# VESC_LANGYA.net
KiCad netlist of a schematic drawn in EasyEDA Pro
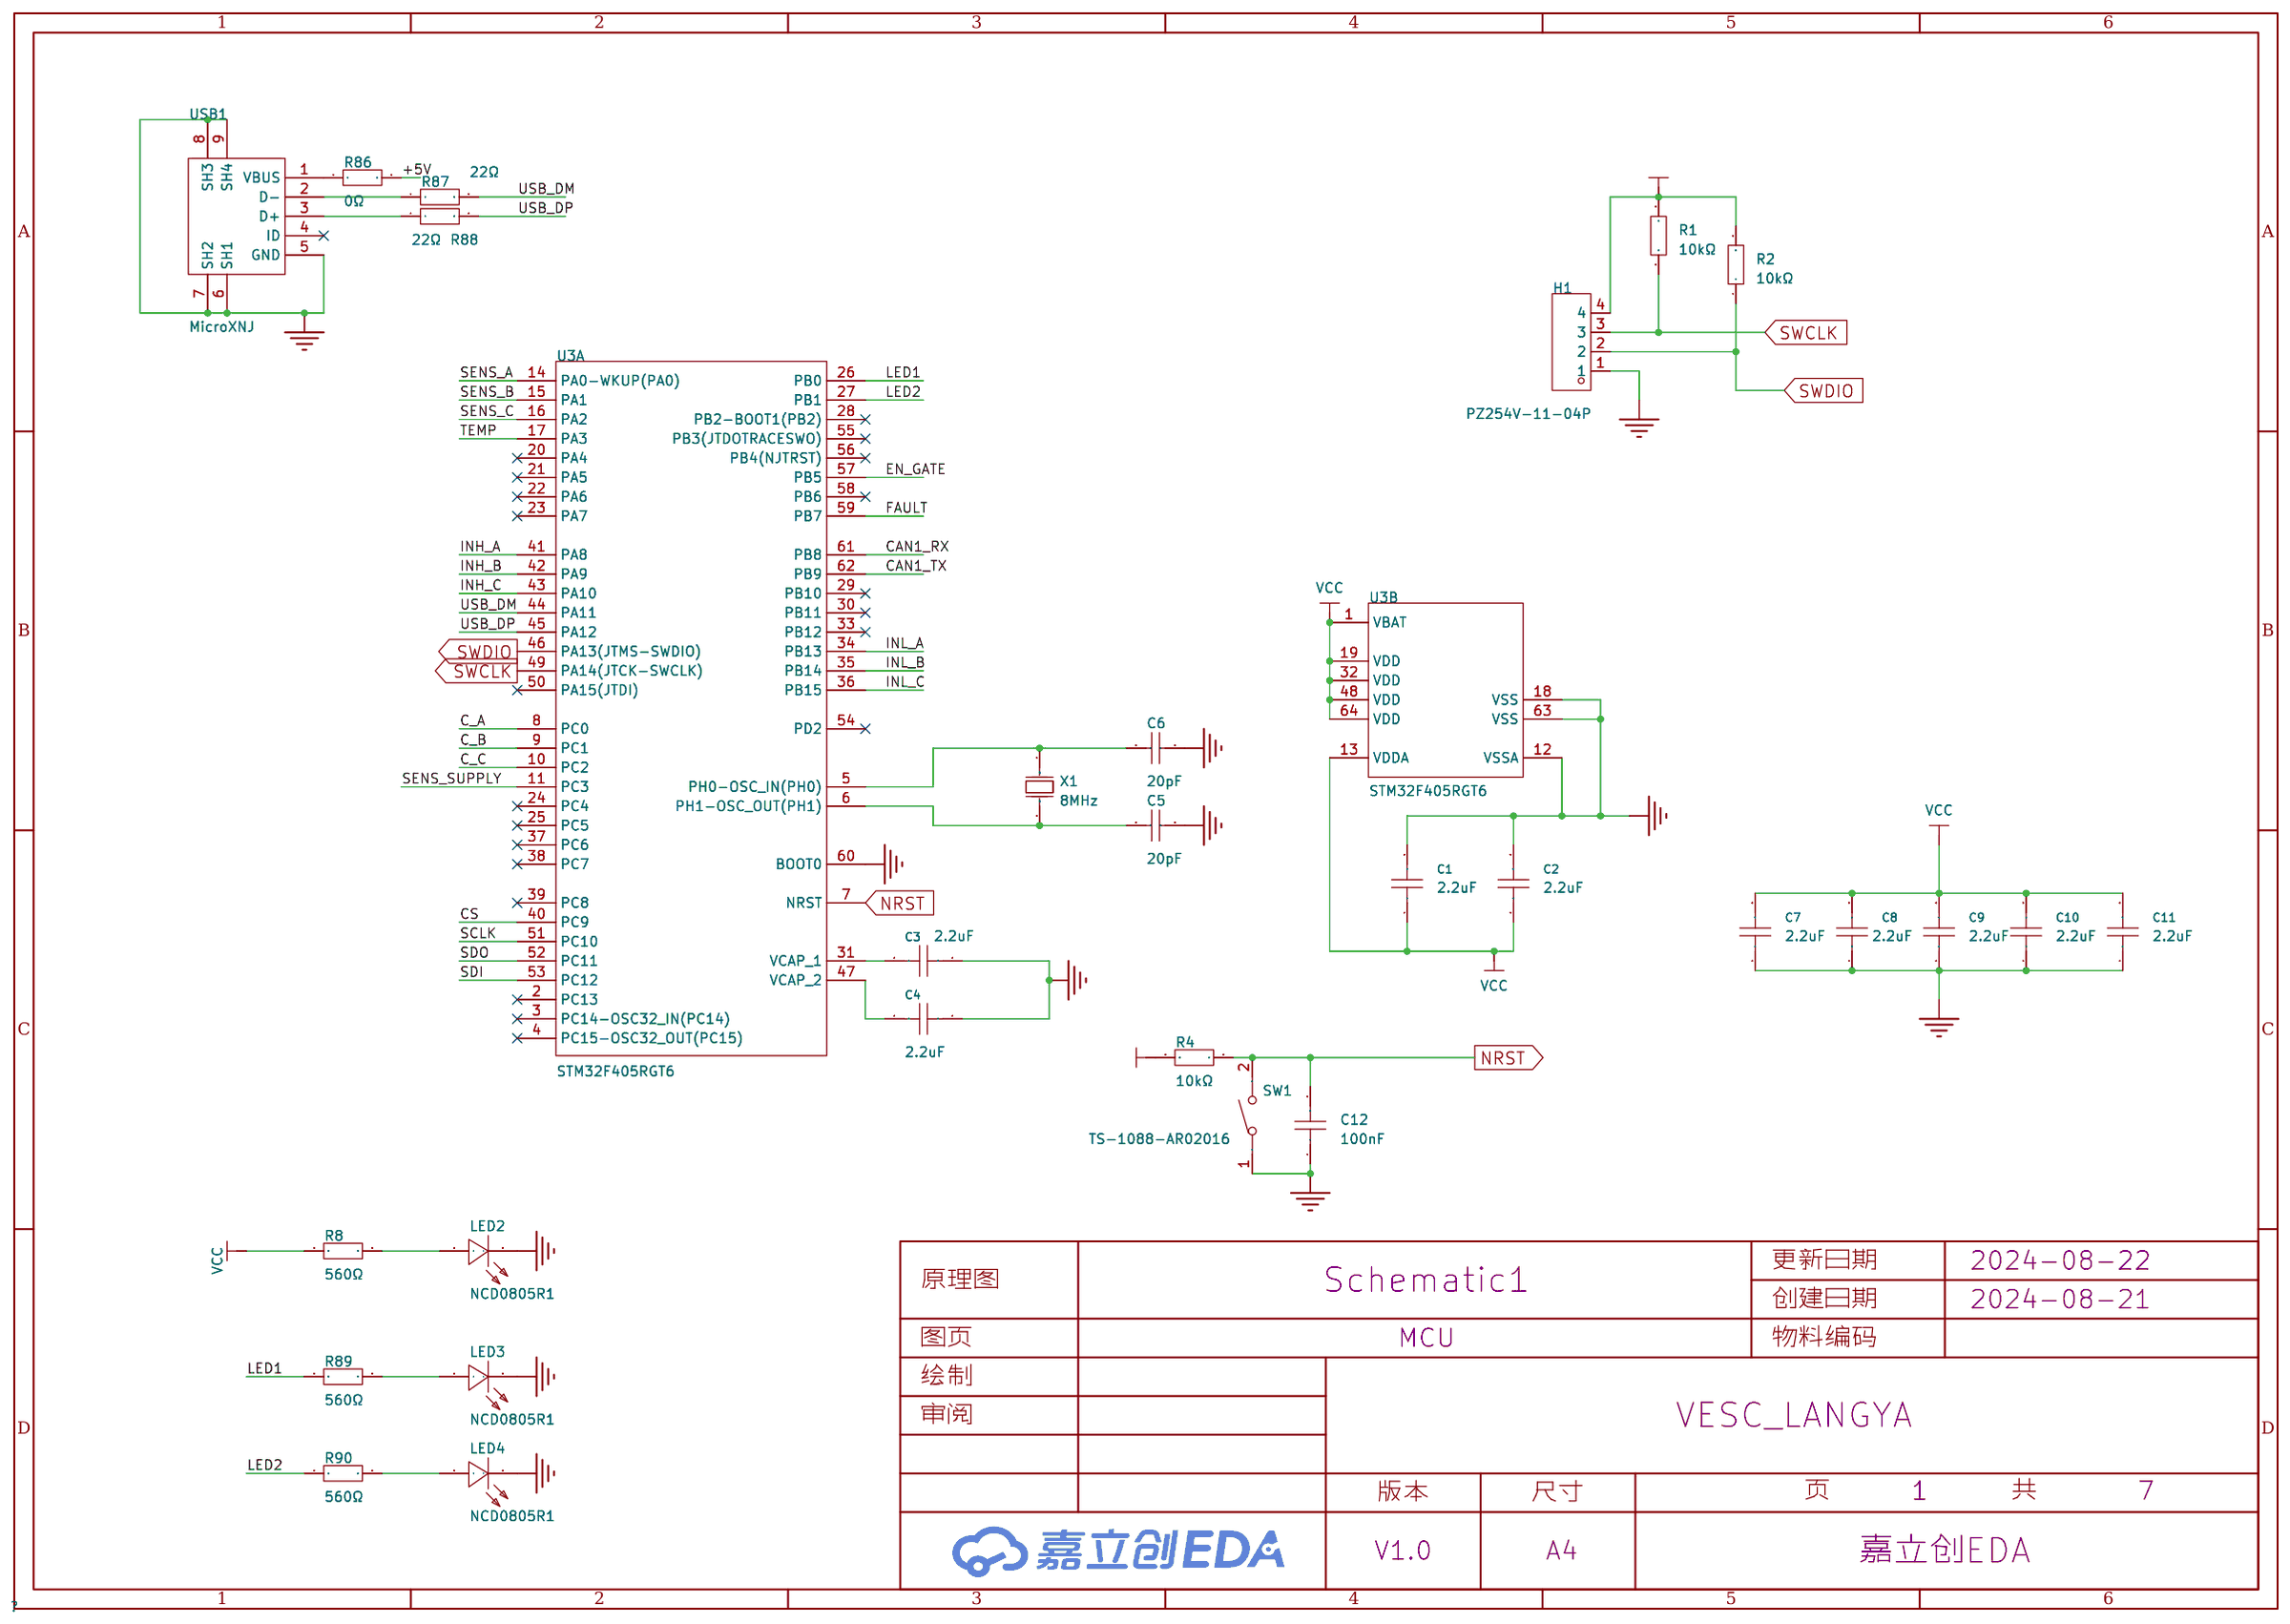
[diagram p0: schematic sheet]

(export (version "E")
  (design (tool "Eeschema 10.0.6"))
  (components
    (comp (ref "C1")
      (value "2.2uF")
      (footprint "easyedapro:C0603")
      (description "容值:2.2uF;精度:±10%;额定电压:50V;材质(温度系数):X5R;")
      (fields
        (field (name "Manufacturer Part") "CL10A225KB8NNNC")
        (field (name "Manufacturer") "SAMSUNG(三星)")
      )
      (libsource (lib "easyedapro") (part "CL10A225KB8NNNC"))
    )
    (comp (ref "C2")
      (value "2.2uF")
      (footprint "easyedapro:C0603")
      (description "容值:2.2uF;精度:±10%;额定电压:50V;材质(温度系数):X5R;")
      (fields
        (field (name "Manufacturer Part") "CL10A225KB8NNNC")
        (field (name "Manufacturer") "SAMSUNG(三星)")
      )
      (libsource (lib "easyedapro") (part "CL10A225KB8NNNC"))
    )
    (comp (ref "C3")
      (value "2.2uF")
      (footprint "easyedapro:C0603")
      (description "容值:2.2uF;精度:±10%;额定电压:50V;材质(温度系数):X5R;")
      (fields
        (field (name "Manufacturer Part") "CL10A225KB8NNNC")
        (field (name "Manufacturer") "SAMSUNG(三星)")
      )
      (libsource (lib "easyedapro") (part "CL10A225KB8NNNC"))
    )
    (comp (ref "C4")
      (value "2.2uF")
      (footprint "easyedapro:C0603")
      (description "容值:2.2uF;精度:±10%;额定电压:50V;材质(温度系数):X5R;")
      (fields
        (field (name "Manufacturer Part") "CL10A225KB8NNNC")
        (field (name "Manufacturer") "SAMSUNG(三星)")
      )
      (libsource (lib "easyedapro") (part "CL10A225KB8NNNC"))
    )
    (comp (ref "C5")
      (value "20pF")
      (footprint "easyedapro:C0603")
      (description "容值:20pF;精度:±5%;额定电压:50V;材质(温度系数):NP0;")
      (fields
        (field (name "Manufacturer Part") "CC0603JRNPO9BN200")
        (field (name "Manufacturer") "YAGEO(国巨)")
      )
      (libsource (lib "easyedapro") (part "CC0603JRNPO9BN200"))
    )
    (comp (ref "C6")
      (value "20pF")
      (footprint "easyedapro:C0603")
      (description "容值:20pF;精度:±5%;额定电压:50V;材质(温度系数):NP0;")
      (fields
        (field (name "Manufacturer Part") "CC0603JRNPO9BN200")
        (field (name "Manufacturer") "YAGEO(国巨)")
      )
      (libsource (lib "easyedapro") (part "CC0603JRNPO9BN200"))
    )
    (comp (ref "C7")
      (value "2.2uF")
      (footprint "easyedapro:C0603")
      (description "容值:2.2uF;精度:±10%;额定电压:50V;材质(温度系数):X5R;")
      (fields
        (field (name "Manufacturer Part") "CL10A225KB8NNNC")
        (field (name "Manufacturer") "SAMSUNG(三星)")
      )
      (libsource (lib "easyedapro") (part "CL10A225KB8NNNC"))
    )
    (comp (ref "C8")
      (value "2.2uF")
      (footprint "easyedapro:C0603")
      (description "容值:2.2uF;精度:±10%;额定电压:50V;材质(温度系数):X5R;")
      (fields
        (field (name "Manufacturer Part") "CL10A225KB8NNNC")
        (field (name "Manufacturer") "SAMSUNG(三星)")
      )
      (libsource (lib "easyedapro") (part "CL10A225KB8NNNC"))
    )
    (comp (ref "C9")
      (value "2.2uF")
      (footprint "easyedapro:C0603")
      (description "容值:2.2uF;精度:±10%;额定电压:50V;材质(温度系数):X5R;")
      (fields
        (field (name "Manufacturer Part") "CL10A225KB8NNNC")
        (field (name "Manufacturer") "SAMSUNG(三星)")
      )
      (libsource (lib "easyedapro") (part "CL10A225KB8NNNC"))
    )
    (comp (ref "C10")
      (value "2.2uF")
      (footprint "easyedapro:C0603")
      (description "容值:2.2uF;精度:±10%;额定电压:50V;材质(温度系数):X5R;")
      (fields
        (field (name "Manufacturer Part") "CL10A225KB8NNNC")
        (field (name "Manufacturer") "SAMSUNG(三星)")
      )
      (libsource (lib "easyedapro") (part "CL10A225KB8NNNC"))
    )
    (comp (ref "C11")
      (value "2.2uF")
      (footprint "easyedapro:C0603")
      (description "容值:2.2uF;精度:±10%;额定电压:50V;材质(温度系数):X5R;")
      (fields
        (field (name "Manufacturer Part") "CL10A225KB8NNNC")
        (field (name "Manufacturer") "SAMSUNG(三星)")
      )
      (libsource (lib "easyedapro") (part "CL10A225KB8NNNC"))
    )
    (comp (ref "C12")
      (value "100nF")
      (footprint "easyedapro:C0603")
      (description "容值:100nF;精度:±10%;额定电压:50V;材质(温度系数):X7R;")
      (fields
        (field (name "Manufacturer Part") "CC0603KRX7R9BB104")
        (field (name "Manufacturer") "YAGEO(国巨)")
      )
      (libsource (lib "easyedapro") (part "CC0603KRX7R9BB104"))
    )
    (comp (ref "H1")
      (value "PZ254V-11-04P")
      (footprint "easyedapro:HDR-TH_4P-P2.54-V-M")
      (fields (field (name "Manufacturer") "XFCN(兴飞)"))
      (libsource (lib "easyedapro") (part "PZ254V-11-04P_C2691448"))
    )
    (comp (ref "LED2")
      (value "NCD0805R1")
      (footprint "easyedapro:LED0805-R-RD")
      (fields (field (name "Manufacturer") "国星光电"))
      (libsource (lib "easyedapro") (part "FC-2012HRK-620D"))
    )
    (comp (ref "LED3")
      (value "NCD0805R1")
      (footprint "easyedapro:LED0805-R-RD")
      (fields (field (name "Manufacturer") "国星光电"))
      (libsource (lib "easyedapro") (part "FC-2012HRK-620D"))
    )
    (comp (ref "LED4")
      (value "NCD0805R1")
      (footprint "easyedapro:LED0805-R-RD")
      (fields (field (name "Manufacturer") "国星光电"))
      (libsource (lib "easyedapro") (part "FC-2012HRK-620D"))
    )
    (comp (ref "R1")
      (value "10kΩ")
      (footprint "easyedapro:R0603")
      (description "电阻类型:厚膜电阻;阻值:10kΩ;精度:±1%;功率:100mW;最大工作电压:75V;温度系数:±100ppm/°C;")
      (fields
        (field (name "Manufacturer Part") "0603WAF1002T5E")
        (field (name "Manufacturer") "UNI-ROYAL(厚声)")
      )
      (libsource (lib "easyedapro") (part "0603WAF1002T5E"))
    )
    (comp (ref "R2")
      (value "10kΩ")
      (footprint "easyedapro:R0603")
      (description "电阻类型:厚膜电阻;阻值:10kΩ;精度:±1%;功率:100mW;最大工作电压:75V;温度系数:±100ppm/°C;")
      (fields
        (field (name "Manufacturer Part") "0603WAF1002T5E")
        (field (name "Manufacturer") "UNI-ROYAL(厚声)")
      )
      (libsource (lib "easyedapro") (part "0603WAF1002T5E"))
    )
    (comp (ref "R4")
      (value "10kΩ")
      (footprint "easyedapro:R0603")
      (description "电阻类型:厚膜电阻;阻值:10kΩ;精度:±1%;功率:100mW;最大工作电压:75V;温度系数:±100ppm/°C;")
      (fields
        (field (name "Manufacturer Part") "0603WAF1002T5E")
        (field (name "Manufacturer") "UNI-ROYAL(厚声)")
      )
      (libsource (lib "easyedapro") (part "0603WAF1002T5E"))
    )
    (comp (ref "R8")
      (value "560Ω")
      (footprint "easyedapro:R0603")
      (description "电阻类型:厚膜电阻;阻值:560Ω;精度:±1%;功率:100mW;最大工作电压:75V;温度系数:±100ppm/°C;")
      (fields
        (field (name "Manufacturer Part") "0603WAF5600T5E")
        (field (name "Manufacturer") "UNI-ROYAL(厚声)")
      )
      (libsource (lib "easyedapro") (part "0603WAF5600T5E"))
    )
    (comp (ref "R86")
      (value "0Ω")
      (footprint "easyedapro:R0603")
      (description "电阻类型:厚膜电阻;阻值:0Ω;精度:±1%;功率:100mW;最大工作电压:75V;")
      (fields
        (field (name "Manufacturer Part") "0603WAF0000T5E")
        (field (name "Manufacturer") "UNI-ROYAL(厚声)")
      )
      (libsource (lib "easyedapro") (part "0603WAF0000T5E"))
    )
    (comp (ref "R87")
      (value "22Ω")
      (footprint "easyedapro:R0603")
      (description "电阻类型:厚膜电阻;阻值:22Ω;精度:±1%;功率:100mW;最大工作电压:75V;温度系数:±100ppm/°C;")
      (fields
        (field (name "Manufacturer Part") "0603WAF220JT5E")
        (field (name "Manufacturer") "UNI-ROYAL(厚声)")
      )
      (libsource (lib "easyedapro") (part "0603WAF220JT5E"))
    )
    (comp (ref "R88")
      (value "22Ω")
      (footprint "easyedapro:R0603")
      (description "电阻类型:厚膜电阻;阻值:22Ω;精度:±1%;功率:100mW;最大工作电压:75V;温度系数:±100ppm/°C;")
      (fields
        (field (name "Manufacturer Part") "0603WAF220JT5E")
        (field (name "Manufacturer") "UNI-ROYAL(厚声)")
      )
      (libsource (lib "easyedapro") (part "0603WAF220JT5E"))
    )
    (comp (ref "R89")
      (value "560Ω")
      (footprint "easyedapro:R0603")
      (description "电阻类型:厚膜电阻;阻值:560Ω;精度:±1%;功率:100mW;最大工作电压:75V;温度系数:±100ppm/°C;")
      (fields
        (field (name "Manufacturer Part") "0603WAF5600T5E")
        (field (name "Manufacturer") "UNI-ROYAL(厚声)")
      )
      (libsource (lib "easyedapro") (part "0603WAF5600T5E"))
    )
    (comp (ref "R90")
      (value "560Ω")
      (footprint "easyedapro:R0603")
      (description "电阻类型:厚膜电阻;阻值:560Ω;精度:±1%;功率:100mW;最大工作电压:75V;温度系数:±100ppm/°C;")
      (fields
        (field (name "Manufacturer Part") "0603WAF5600T5E")
        (field (name "Manufacturer") "UNI-ROYAL(厚声)")
      )
      (libsource (lib "easyedapro") (part "0603WAF5600T5E"))
    )
    (comp (ref "SW1")
      (value "TS-1088-AR02016")
      (footprint "easyedapro:SW-SMD_L3.9-W3.0-P4.45")
      (fields (field (name "Manufacturer") "XUNPU(讯普)"))
      (libsource (lib "easyedapro") (part "TS-1088-AR02016"))
    )
    (comp (ref "U3")
      (value "STM32F405RGT6")
      (footprint "easyedapro:LQFP-64_L10.0-W10.0-P0.50-LS12.0-BL")
      (description "CPU内核:ARM-M4;程序存储容量:1MB;RAM总容量:192KB;GPIO端口数量:51;工作电压范围:1.8V~3.6V;CPU最大主频:168MHz;程序存储器类型:FLASH;")
      (fields (field (name "Manufacturer") "ST(意法半导体)"))
      (libsource (lib "easyedapro") (part "STM32F405RGT6"))
    )
    (comp (ref "USB1")
      (value "MicroXNJ")
      (footprint "easyedapro:MICRO-USB-SMD_MICROXNJ")
      (description "连接器类型:Micro-B;标准:USB 2.0;公母:母;安装方式:卧贴;触点数量:5P;端口数量:1;额定电流 - 电源:1A;工作温度范围:-20°C~+85°C;")
      (fields (field (name "Manufacturer") "SHOU HAN(首韩)"))
      (libsource (lib "easyedapro") (part "MICROXNJ"))
    )
    (comp (ref "X1")
      (value "8MHz")
      (footprint "easyedapro:CRYSTAL-SMD_L5.0-W3.2")
      (description "晶振类型:贴片晶振;频率:8MHz;常温频差:±10ppm;外接负载电容:20pF;频率稳定度(全温):±20ppm;")
      (fields (field (name "Manufacturer Part") "X50328MSB2GI") (field (name "Manufacturer") "YXC(扬兴晶振)"))
      (libsource (lib "easyedapro") (part "X50328MSB2GI"))
    )
  )
  (nets
    (net (code "1") (name "/+5V") (class "Default")
      (node (ref "R86") (pin "2") (pinfunction "2_2") (pintype "input"))
    )
    (net (code "2") (name "/CAN1_RX") (class "Default")
      (node (ref "U3") (pin "61") (pinfunction "PB8_61") (pintype "bidirectional"))
    )
    (net (code "3") (name "/CAN1_TX") (class "Default")
      (node (ref "U3") (pin "62") (pinfunction "PB9_62") (pintype "bidirectional"))
    )
    (net (code "4") (name "/CS") (class "Default")
      (node (ref "U3") (pin "40") (pinfunction "PC9_40") (pintype "bidirectional"))
    )
    (net (code "5") (name "/C_A") (class "Default")
      (node (ref "U3") (pin "8") (pinfunction "PC0_8") (pintype "bidirectional"))
    )
    (net (code "6") (name "/C_B") (class "Default")
      (node (ref "U3") (pin "9") (pinfunction "PC1_9") (pintype "bidirectional"))
    )
    (net (code "7") (name "/C_C") (class "Default")
      (node (ref "U3") (pin "10") (pinfunction "PC2_10") (pintype "bidirectional"))
    )
    (net (code "8") (name "/EN_GATE") (class "Default")
      (node (ref "U3") (pin "57") (pinfunction "PB5_57") (pintype "bidirectional"))
    )
    (net (code "9") (name "/FAULT") (class "Default")
      (node (ref "U3") (pin "59") (pinfunction "PB7_59") (pintype "bidirectional"))
    )
    (net (code "10") (name "/INH_A") (class "Default")
      (node (ref "U3") (pin "41") (pinfunction "PA8_41") (pintype "bidirectional"))
    )
    (net (code "11") (name "/INH_B") (class "Default")
      (node (ref "U3") (pin "42") (pinfunction "PA9_42") (pintype "bidirectional"))
    )
    (net (code "12") (name "/INH_C") (class "Default")
      (node (ref "U3") (pin "43") (pinfunction "PA10_43") (pintype "bidirectional"))
    )
    (net (code "13") (name "/INL_A") (class "Default")
      (node (ref "U3") (pin "34") (pinfunction "PB13_34") (pintype "bidirectional"))
    )
    (net (code "14") (name "/INL_B") (class "Default")
      (node (ref "U3") (pin "35") (pinfunction "PB14_35") (pintype "bidirectional"))
    )
    (net (code "15") (name "/INL_C") (class "Default")
      (node (ref "U3") (pin "36") (pinfunction "PB15_36") (pintype "bidirectional"))
    )
    (net (code "16") (name "/LED1") (class "Default")
      (node (ref "R89") (pin "1") (pinfunction "1_1") (pintype "input"))
      (node (ref "U3") (pin "26") (pinfunction "PB0_26") (pintype "bidirectional"))
    )
    (net (code "17") (name "/LED2") (class "Default")
      (node (ref "R90") (pin "1") (pinfunction "1_1") (pintype "input"))
      (node (ref "U3") (pin "27") (pinfunction "PB1_27") (pintype "bidirectional"))
    )
    (net (code "18") (name "/SCLK") (class "Default")
      (node (ref "U3") (pin "51") (pinfunction "PC10_51") (pintype "bidirectional"))
    )
    (net (code "19") (name "/SDI") (class "Default")
      (node (ref "U3") (pin "53") (pinfunction "PC12_53") (pintype "bidirectional"))
    )
    (net (code "20") (name "/SDO") (class "Default")
      (node (ref "U3") (pin "52") (pinfunction "PC11_52") (pintype "bidirectional"))
    )
    (net (code "21") (name "/SENS_A") (class "Default")
      (node (ref "U3") (pin "14") (pinfunction "PA0-WKUP(PA0)_14") (pintype "bidirectional"))
    )
    (net (code "22") (name "/SENS_B") (class "Default")
      (node (ref "U3") (pin "15") (pinfunction "PA1_15") (pintype "bidirectional"))
    )
    (net (code "23") (name "/SENS_C") (class "Default")
      (node (ref "U3") (pin "16") (pinfunction "PA2_16") (pintype "bidirectional"))
    )
    (net (code "24") (name "/SENS_SUPPLY") (class "Default")
      (node (ref "U3") (pin "11") (pinfunction "PC3_11") (pintype "bidirectional"))
    )
    (net (code "25") (name "/TEMP") (class "Default")
      (node (ref "U3") (pin "17") (pinfunction "PA3_17") (pintype "bidirectional"))
    )
    (net (code "26") (name "/USB_DM") (class "Default")
      (node (ref "R87") (pin "2") (pinfunction "2_2") (pintype "input"))
      (node (ref "U3") (pin "44") (pinfunction "PA11_44") (pintype "bidirectional"))
    )
    (net (code "27") (name "/USB_DP") (class "Default")
      (node (ref "R88") (pin "2") (pinfunction "2_2") (pintype "input"))
      (node (ref "U3") (pin "45") (pinfunction "PA12_45") (pintype "bidirectional"))
    )
    (net (code "28") (name "GND") (class "Default")
      (node (ref "C1") (pin "2") (pinfunction "2_2") (pintype "input"))
      (node (ref "C10") (pin "1") (pinfunction "1_1") (pintype "input"))
      (node (ref "C11") (pin "1") (pinfunction "1_1") (pintype "input"))
      (node (ref "C12") (pin "1") (pinfunction "1_1") (pintype "unspecified"))
      (node (ref "C2") (pin "2") (pinfunction "2_2") (pintype "input"))
      (node (ref "C3") (pin "1") (pinfunction "1_1") (pintype "input"))
      (node (ref "C4") (pin "1") (pinfunction "1_1") (pintype "input"))
      (node (ref "C5") (pin "1") (pinfunction "1_1") (pintype "input"))
      (node (ref "C6") (pin "1") (pinfunction "1_1") (pintype "input"))
      (node (ref "C7") (pin "1") (pinfunction "1_1") (pintype "input"))
      (node (ref "C8") (pin "1") (pinfunction "1_1") (pintype "input"))
      (node (ref "C9") (pin "1") (pinfunction "1_1") (pintype "input"))
      (node (ref "H1") (pin "1") (pinfunction "1_1") (pintype "unspecified"))
      (node (ref "LED2") (pin "2") (pinfunction "-_2") (pintype "unspecified"))
      (node (ref "LED3") (pin "2") (pinfunction "-_2") (pintype "unspecified"))
      (node (ref "LED4") (pin "2") (pinfunction "-_2") (pintype "unspecified"))
      (node (ref "SW1") (pin "1") (pinfunction "1_1") (pintype "unspecified"))
      (node (ref "U3") (pin "12") (pinfunction "VSSA_12") (pintype "unspecified"))
      (node (ref "U3") (pin "18") (pinfunction "VSS_18") (pintype "unspecified"))
      (node (ref "U3") (pin "60") (pinfunction "BOOT0_60") (pintype "unspecified"))
      (node (ref "U3") (pin "63") (pinfunction "VSS_63") (pintype "unspecified"))
      (node (ref "USB1") (pin "5") (pinfunction "GND_5") (pintype "unspecified"))
      (node (ref "USB1") (pin "6") (pinfunction "SH1_6") (pintype "unspecified"))
      (node (ref "USB1") (pin "7") (pinfunction "SH2_7") (pintype "unspecified"))
      (node (ref "USB1") (pin "8") (pinfunction "SH3_8") (pintype "unspecified"))
      (node (ref "USB1") (pin "9") (pinfunction "SH4_9") (pintype "unspecified"))
    )
    (net (code "29") (name "NRST") (class "Default")
      (node (ref "C12") (pin "2") (pinfunction "2_2") (pintype "unspecified"))
      (node (ref "R4") (pin "1") (pinfunction "1_1") (pintype "input"))
      (node (ref "SW1") (pin "2") (pinfunction "2_2") (pintype "unspecified"))
      (node (ref "U3") (pin "7") (pinfunction "NRST_7") (pintype "bidirectional"))
    )
    (net (code "30") (name "Net-(LED2-+)") (class "Default")
      (node (ref "LED2") (pin "1") (pinfunction "+_1") (pintype "unspecified"))
      (node (ref "R8") (pin "2") (pinfunction "2_2") (pintype "input"))
    )
    (net (code "31") (name "Net-(LED3-+)") (class "Default")
      (node (ref "LED3") (pin "1") (pinfunction "+_1") (pintype "unspecified"))
      (node (ref "R89") (pin "2") (pinfunction "2_2") (pintype "input"))
    )
    (net (code "32") (name "Net-(LED4-+)") (class "Default")
      (node (ref "LED4") (pin "1") (pinfunction "+_1") (pintype "unspecified"))
      (node (ref "R90") (pin "2") (pinfunction "2_2") (pintype "input"))
    )
    (net (code "33") (name "Net-(U3A-PH0-OSC_IN(PH0))") (class "Default")
      (node (ref "C6") (pin "2") (pinfunction "2_2") (pintype "input"))
      (node (ref "U3") (pin "5") (pinfunction "PH0-OSC_IN(PH0)_5") (pintype "bidirectional"))
      (node (ref "X1") (pin "1") (pinfunction "OSC1_1") (pintype "input"))
    )
    (net (code "34") (name "Net-(U3A-PH1-OSC_OUT(PH1))") (class "Default")
      (node (ref "C5") (pin "2") (pinfunction "2_2") (pintype "input"))
      (node (ref "U3") (pin "6") (pinfunction "PH1-OSC_OUT(PH1)_6") (pintype "bidirectional"))
      (node (ref "X1") (pin "2") (pinfunction "OSC2_2") (pintype "input"))
    )
    (net (code "35") (name "Net-(U3A-VCAP_1)") (class "Default")
      (node (ref "C3") (pin "2") (pinfunction "2_2") (pintype "input"))
      (node (ref "U3") (pin "31") (pinfunction "VCAP_1_31") (pintype "unspecified"))
    )
    (net (code "36") (name "Net-(U3A-VCAP_2)") (class "Default")
      (node (ref "C4") (pin "2") (pinfunction "2_2") (pintype "input"))
      (node (ref "U3") (pin "47") (pinfunction "VCAP_2_47") (pintype "unspecified"))
    )
    (net (code "37") (name "Net-(USB1-D+)") (class "Default")
      (node (ref "R88") (pin "1") (pinfunction "1_1") (pintype "input"))
      (node (ref "USB1") (pin "3") (pinfunction "D+_3") (pintype "unspecified"))
    )
    (net (code "38") (name "Net-(USB1-D-)") (class "Default")
      (node (ref "R87") (pin "1") (pinfunction "1_1") (pintype "input"))
      (node (ref "USB1") (pin "2") (pinfunction "D-_2") (pintype "unspecified"))
    )
    (net (code "39") (name "Net-(USB1-VBUS)") (class "Default")
      (node (ref "R86") (pin "1") (pinfunction "1_1") (pintype "input"))
      (node (ref "USB1") (pin "1") (pinfunction "VBUS_1") (pintype "unspecified"))
    )
    (net (code "40") (name "SWCLK") (class "Default")
      (node (ref "H1") (pin "3") (pinfunction "3_3") (pintype "unspecified"))
      (node (ref "R1") (pin "1") (pinfunction "1_1") (pintype "input"))
      (node (ref "U3") (pin "49") (pinfunction "PA14(JTCK-SWCLK)_49") (pintype "bidirectional"))
    )
    (net (code "41") (name "SWDIO") (class "Default")
      (node (ref "H1") (pin "2") (pinfunction "2_2") (pintype "unspecified"))
      (node (ref "R2") (pin "1") (pinfunction "1_1") (pintype "input"))
      (node (ref "U3") (pin "46") (pinfunction "PA13(JTMS-SWDIO)_46") (pintype "bidirectional"))
    )
    (net (code "42") (name "VCC") (class "Default")
      (node (ref "C1") (pin "1") (pinfunction "1_1") (pintype "input"))
      (node (ref "C10") (pin "2") (pinfunction "2_2") (pintype "input"))
      (node (ref "C11") (pin "2") (pinfunction "2_2") (pintype "input"))
      (node (ref "C2") (pin "1") (pinfunction "1_1") (pintype "input"))
      (node (ref "C7") (pin "2") (pinfunction "2_2") (pintype "input"))
      (node (ref "C8") (pin "2") (pinfunction "2_2") (pintype "input"))
      (node (ref "C9") (pin "2") (pinfunction "2_2") (pintype "input"))
      (node (ref "H1") (pin "4") (pinfunction "4_4") (pintype "unspecified"))
      (node (ref "R1") (pin "2") (pinfunction "2_2") (pintype "input"))
      (node (ref "R2") (pin "2") (pinfunction "2_2") (pintype "input"))
      (node (ref "R4") (pin "2") (pinfunction "2_2") (pintype "input"))
      (node (ref "R8") (pin "1") (pinfunction "1_1") (pintype "input"))
      (node (ref "U3") (pin "1") (pinfunction "VBAT_1") (pintype "unspecified"))
      (node (ref "U3") (pin "13") (pinfunction "VDDA_13") (pintype "unspecified"))
      (node (ref "U3") (pin "19") (pinfunction "VDD_19") (pintype "unspecified"))
      (node (ref "U3") (pin "32") (pinfunction "VDD_32") (pintype "unspecified"))
      (node (ref "U3") (pin "48") (pinfunction "VDD_48") (pintype "unspecified"))
      (node (ref "U3") (pin "64") (pinfunction "VDD_64") (pintype "unspecified"))
    )
    (net (code "43") (name "unconnected-(U3A-PA4-Pad20)") (class "Default")
      (node (ref "U3") (pin "20") (pinfunction "PA4_20") (pintype "bidirectional+no_connect"))
    )
    (net (code "44") (name "unconnected-(U3A-PA5-Pad21)") (class "Default")
      (node (ref "U3") (pin "21") (pinfunction "PA5_21") (pintype "bidirectional+no_connect"))
    )
    (net (code "45") (name "unconnected-(U3A-PA6-Pad22)") (class "Default")
      (node (ref "U3") (pin "22") (pinfunction "PA6_22") (pintype "bidirectional+no_connect"))
    )
    (net (code "46") (name "unconnected-(U3A-PA7-Pad23)") (class "Default")
      (node (ref "U3") (pin "23") (pinfunction "PA7_23") (pintype "bidirectional+no_connect"))
    )
    (net (code "47") (name "unconnected-(U3A-PA15(JTDI)-Pad50)") (class "Default")
      (node (ref "U3") (pin "50") (pinfunction "PA15(JTDI)_50") (pintype "bidirectional+no_connect"))
    )
    (net (code "48") (name "unconnected-(U3A-PB2-BOOT1(PB2)-Pad28)") (class "Default")
      (node (ref "U3") (pin "28") (pinfunction "PB2-BOOT1(PB2)_28") (pintype "bidirectional+no_connect"))
    )
    (net (code "49") (name "unconnected-(U3A-PB3(JTDOTRACESWO)-Pad55)") (class "Default")
      (node (ref "U3") (pin "55") (pinfunction "PB3(JTDOTRACESWO)_55") (pintype "bidirectional+no_connect"))
    )
    (net (code "50") (name "unconnected-(U3A-PB4(NJTRST)-Pad56)") (class "Default")
      (node (ref "U3") (pin "56") (pinfunction "PB4(NJTRST)_56") (pintype "bidirectional+no_connect"))
    )
    (net (code "51") (name "unconnected-(U3A-PB6-Pad58)") (class "Default")
      (node (ref "U3") (pin "58") (pinfunction "PB6_58") (pintype "bidirectional+no_connect"))
    )
    (net (code "52") (name "unconnected-(U3A-PB10-Pad29)") (class "Default")
      (node (ref "U3") (pin "29") (pinfunction "PB10_29") (pintype "bidirectional+no_connect"))
    )
    (net (code "53") (name "unconnected-(U3A-PB11-Pad30)") (class "Default")
      (node (ref "U3") (pin "30") (pinfunction "PB11_30") (pintype "bidirectional+no_connect"))
    )
    (net (code "54") (name "unconnected-(U3A-PB12-Pad33)") (class "Default")
      (node (ref "U3") (pin "33") (pinfunction "PB12_33") (pintype "bidirectional+no_connect"))
    )
    (net (code "55") (name "unconnected-(U3A-PC4-Pad24)") (class "Default")
      (node (ref "U3") (pin "24") (pinfunction "PC4_24") (pintype "bidirectional+no_connect"))
    )
    (net (code "56") (name "unconnected-(U3A-PC5-Pad25)") (class "Default")
      (node (ref "U3") (pin "25") (pinfunction "PC5_25") (pintype "bidirectional+no_connect"))
    )
    (net (code "57") (name "unconnected-(U3A-PC6-Pad37)") (class "Default")
      (node (ref "U3") (pin "37") (pinfunction "PC6_37") (pintype "bidirectional+no_connect"))
    )
    (net (code "58") (name "unconnected-(U3A-PC7-Pad38)") (class "Default")
      (node (ref "U3") (pin "38") (pinfunction "PC7_38") (pintype "bidirectional+no_connect"))
    )
    (net (code "59") (name "unconnected-(U3A-PC8-Pad39)") (class "Default")
      (node (ref "U3") (pin "39") (pinfunction "PC8_39") (pintype "bidirectional+no_connect"))
    )
    (net (code "60") (name "unconnected-(U3A-PC13-Pad2)") (class "Default")
      (node (ref "U3") (pin "2") (pinfunction "PC13_2") (pintype "bidirectional+no_connect"))
    )
    (net (code "61") (name "unconnected-(U3A-PC14-OSC32_IN(PC14)-Pad3)") (class "Default")
      (node (ref "U3") (pin "3") (pinfunction "PC14-OSC32_IN(PC14)_3") (pintype "bidirectional+no_connect"))
    )
    (net (code "62") (name "unconnected-(U3A-PC15-OSC32_OUT(PC15)-Pad4)") (class "Default")
      (node (ref "U3") (pin "4") (pinfunction "PC15-OSC32_OUT(PC15)_4") (pintype "bidirectional+no_connect"))
    )
    (net (code "63") (name "unconnected-(U3A-PD2-Pad54)") (class "Default")
      (node (ref "U3") (pin "54") (pinfunction "PD2_54") (pintype "bidirectional+no_connect"))
    )
    (net (code "64") (name "unconnected-(USB1-ID-Pad4)") (class "Default")
      (node (ref "USB1") (pin "4") (pinfunction "ID_4") (pintype "unspecified+no_connect"))
    )
  )
)
